# IB_VBE.net
KiCad netlist of a schematic drawn in Altium Designer
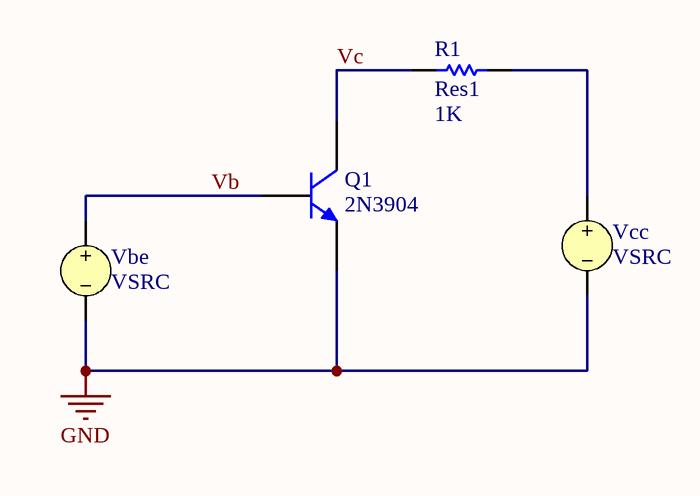
[diagram p0: IB_VBE.SchDoc]

(export (version "E")
  (design (tool "Eeschema 10.0.6"))
  (components
    (comp (ref "Q1")
      (value "2N3904")
      (footprint "TO-92A")
      (description "NPN General Purpose Amplifier")
      (fields (field (name "PUBLISHER") "Altium Limited"))
      (libsource (lib "Miscellaneous Devices") (part "2N3904"))
    )
    (comp (ref "R1")
      (value "Res1")
      (footprint "AXIAL-0.3")
      (description "Resistor")
      (fields (field (name "ALTIUM_VALUE") "1K") (field (name "PUBLISHER") "Altium Limited"))
      (libsource (lib "Miscellaneous Devices") (part "Res1"))
    )
    (comp (ref "Vbe")
      (value "VSRC")
      (description "Voltage Source")
      (fields (field (name "PUBLISHER") "Altium Limited"))
      (libsource (lib "Simulation Sources") (part "VSRC"))
    )
    (comp (ref "Vcc")
      (value "VSRC")
      (description "Voltage Source")
      (fields (field (name "PUBLISHER") "Altium Limited"))
      (libsource (lib "Simulation Sources") (part "VSRC"))
    )
  )
  (nets
    (net (code "1") (name "/Vb") (class "Default")
      (node (ref "Q1") (pin "2") (pinfunction "B_2") (pintype "passive"))
      (node (ref "Vbe") (pin "1") (pinfunction "1_1") (pintype "passive"))
    )
    (net (code "2") (name "/Vc") (class "Default")
      (node (ref "Q1") (pin "3") (pinfunction "C_3") (pintype "passive"))
      (node (ref "R1") (pin "1") (pinfunction "1_1") (pintype "passive"))
    )
    (net (code "3") (name "GND") (class "Default")
      (node (ref "Q1") (pin "1") (pinfunction "E_1") (pintype "passive"))
      (node (ref "Vbe") (pin "2") (pinfunction "2_2") (pintype "passive"))
      (node (ref "Vcc") (pin "2") (pinfunction "2_2") (pintype "passive"))
    )
    (net (code "4") (name "Net-(R1-Pad2)") (class "Default")
      (node (ref "R1") (pin "2") (pinfunction "2_2") (pintype "passive"))
      (node (ref "Vcc") (pin "1") (pinfunction "1_1") (pintype "passive"))
    )
  )
)
